# Sch_v4.net
KiCad netlist of a schematic drawn in EAGLE
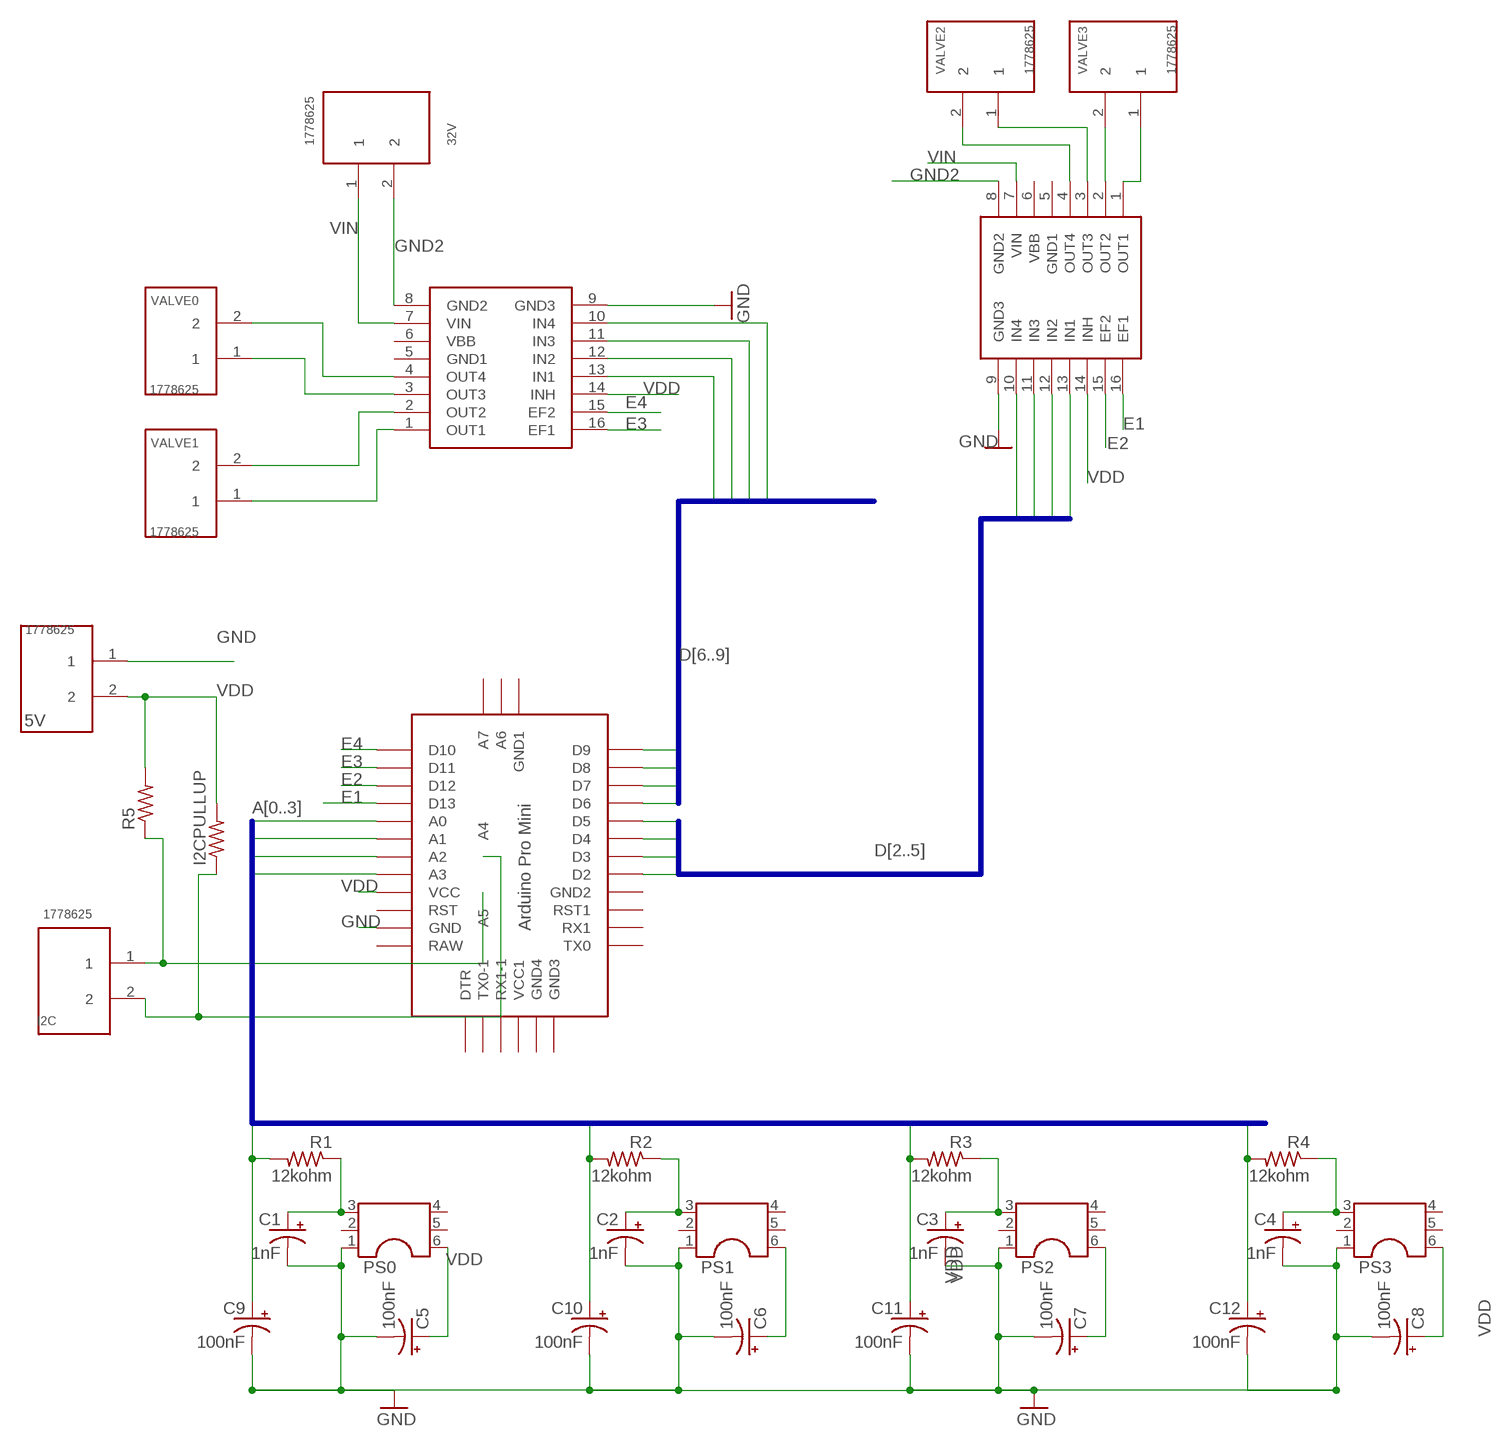
[diagram p0: schematic, sheet 1]

(export (version "E")
  (design (tool "Eeschema 10.0.6"))
  (components
    (comp (ref "5V")
      (value "1778625")
      (footprint "eagle-import:1778625")
      (fields (field (name "MF") "Phoenix Contact"))
      (libsource (lib "eagle-import") (part "1778625"))
    )
    (comp (ref "32V")
      (value "1778625")
      (footprint "eagle-import:1778625")
      (fields (field (name "MF") "Phoenix Contact"))
      (libsource (lib "eagle-import") (part "1778625"))
    )
    (comp (ref "C1")
      (value "1nF")
      (footprint "eagle-import:E2,5-5")
      (libsource (lib "eagle-import") (part "CPOL-USE2.5-5"))
    )
    (comp (ref "C2")
      (value "1nF")
      (footprint "eagle-import:E2,5-5")
      (libsource (lib "eagle-import") (part "CPOL-USE2.5-5"))
    )
    (comp (ref "C3")
      (value "1nF")
      (footprint "eagle-import:E2,5-5")
      (libsource (lib "eagle-import") (part "CPOL-USE2.5-5"))
    )
    (comp (ref "C4")
      (value "1nF")
      (footprint "eagle-import:E2,5-5")
      (libsource (lib "eagle-import") (part "CPOL-USE2.5-5"))
    )
    (comp (ref "C5")
      (value "100nF")
      (footprint "eagle-import:E2,5-5")
      (libsource (lib "eagle-import") (part "CPOL-USE2.5-5"))
    )
    (comp (ref "C6")
      (value "100nF")
      (footprint "eagle-import:E2,5-5")
      (libsource (lib "eagle-import") (part "CPOL-USE2.5-5"))
    )
    (comp (ref "C7")
      (value "100nF")
      (footprint "eagle-import:E2,5-5")
      (libsource (lib "eagle-import") (part "CPOL-USE2.5-5"))
    )
    (comp (ref "C8")
      (value "100nF")
      (footprint "eagle-import:E2,5-5")
      (libsource (lib "eagle-import") (part "CPOL-USE2.5-5"))
    )
    (comp (ref "C9")
      (value "100nF")
      (footprint "eagle-import:E2,5-5")
      (libsource (lib "eagle-import") (part "CPOL-USE2.5-5"))
    )
    (comp (ref "C10")
      (value "100nF")
      (footprint "eagle-import:E2,5-5")
      (libsource (lib "eagle-import") (part "CPOL-USE2.5-5"))
    )
    (comp (ref "C11")
      (value "100nF")
      (footprint "eagle-import:E2,5-5")
      (libsource (lib "eagle-import") (part "CPOL-USE2.5-5"))
    )
    (comp (ref "C12")
      (value "100nF")
      (footprint "eagle-import:E2,5-5")
      (libsource (lib "eagle-import") (part "CPOL-USE2.5-5"))
    )
    (comp (ref "I2C")
      (value "1778625")
      (footprint "eagle-import:1778625")
      (fields (field (name "MF") "Phoenix Contact"))
      (libsource (lib "eagle-import") (part "1778625"))
    )
    (comp (ref "I2CPULLUP")
      (value "R-US_0204/7")
      (footprint "eagle-import:0204_7")
      (libsource (lib "eagle-import") (part "R-US_0204/7"))
    )
    (comp (ref "PS0")
      (value "ABPDRNN100PGAA5")
      (footprint "eagle-import:ABPDRNN100PGAA5")
      (libsource (lib "eagle-import") (part "ABPDRNN100PGAA5"))
    )
    (comp (ref "PS1")
      (value "ABPDRNN100PGAA5")
      (footprint "eagle-import:ABPDRNN100PGAA5")
      (libsource (lib "eagle-import") (part "ABPDRNN100PGAA5"))
    )
    (comp (ref "PS2")
      (value "ABPDRNN100PGAA5")
      (footprint "eagle-import:ABPDRNN100PGAA5")
      (libsource (lib "eagle-import") (part "ABPDRNN100PGAA5"))
    )
    (comp (ref "PS3")
      (value "ABPDRNN100PGAA5")
      (footprint "eagle-import:ABPDRNN100PGAA5")
      (libsource (lib "eagle-import") (part "ABPDRNN100PGAA5"))
    )
    (comp (ref "R1")
      (value "12kohm")
      (footprint "eagle-import:0204_7")
      (libsource (lib "eagle-import") (part "R-US_0204/7"))
    )
    (comp (ref "R2")
      (value "12kohm")
      (footprint "eagle-import:0204_7")
      (libsource (lib "eagle-import") (part "R-US_0204/7"))
    )
    (comp (ref "R3")
      (value "12kohm")
      (footprint "eagle-import:0204_7")
      (libsource (lib "eagle-import") (part "R-US_0204/7"))
    )
    (comp (ref "R4")
      (value "12kohm")
      (footprint "eagle-import:0204_7")
      (libsource (lib "eagle-import") (part "R-US_0204/7"))
    )
    (comp (ref "R5")
      (value "R-US_0204/7")
      (footprint "eagle-import:0204_7")
      (libsource (lib "eagle-import") (part "R-US_0204/7"))
    )
    (comp (ref "U$1")
      (value "ABK-PRO-MINI")
      (footprint "eagle-import:ABK-PRO-MINI")
      (libsource (lib "eagle-import") (part "ABK-PRO-MINI"))
    )
    (comp (ref "U$2")
      (value "A4990")
      (footprint "eagle-import:A4990")
      (libsource (lib "eagle-import") (part "A4990"))
    )
    (comp (ref "U$3")
      (value "A4990")
      (footprint "eagle-import:A4990")
      (libsource (lib "eagle-import") (part "A4990"))
    )
    (comp (ref "VALVE0")
      (value "1778625")
      (footprint "eagle-import:1778625")
      (fields (field (name "MF") "Phoenix Contact"))
      (libsource (lib "eagle-import") (part "1778625"))
    )
    (comp (ref "VALVE1")
      (value "1778625")
      (footprint "eagle-import:1778625")
      (fields (field (name "MF") "Phoenix Contact"))
      (libsource (lib "eagle-import") (part "1778625"))
    )
    (comp (ref "VALVE2")
      (value "1778625")
      (footprint "eagle-import:1778625")
      (fields (field (name "MF") "Phoenix Contact"))
      (libsource (lib "eagle-import") (part "1778625"))
    )
    (comp (ref "VALVE3")
      (value "1778625")
      (footprint "eagle-import:1778625")
      (fields (field (name "MF") "Phoenix Contact"))
      (libsource (lib "eagle-import") (part "1778625"))
    )
  )
  (nets
    (net (code "1") (name "/A0") (class "Default")
      (node (ref "C9") (pin "+") (pinfunction "+_+") (pintype "passive"))
      (node (ref "R1") (pin "2") (pinfunction "2_2") (pintype "passive"))
      (node (ref "U$1") (pin "A0") (pinfunction "A0_A0") (pintype "bidirectional"))
    )
    (net (code "2") (name "/A1") (class "Default")
      (node (ref "C10") (pin "+") (pinfunction "+_+") (pintype "passive"))
      (node (ref "R2") (pin "2") (pinfunction "2_2") (pintype "passive"))
      (node (ref "U$1") (pin "A1") (pinfunction "A1_A1") (pintype "bidirectional"))
    )
    (net (code "3") (name "/A2") (class "Default")
      (node (ref "C11") (pin "+") (pinfunction "+_+") (pintype "passive"))
      (node (ref "R3") (pin "2") (pinfunction "2_2") (pintype "passive"))
      (node (ref "U$1") (pin "A2") (pinfunction "A2_A2") (pintype "bidirectional"))
    )
    (net (code "4") (name "/A3") (class "Default")
      (node (ref "C12") (pin "+") (pinfunction "+_+") (pintype "passive"))
      (node (ref "R4") (pin "2") (pinfunction "2_2") (pintype "passive"))
      (node (ref "U$1") (pin "A3") (pinfunction "A3_A3") (pintype "bidirectional"))
    )
    (net (code "6") (name "/D2") (class "Default")
      (node (ref "U$1") (pin "D2") (pinfunction "D2_D2") (pintype "bidirectional"))
      (node (ref "U$3") (pin "13") (pinfunction "IN1_13") (pintype "bidirectional"))
    )
    (net (code "7") (name "/D3") (class "Default")
      (node (ref "U$1") (pin "D3") (pinfunction "D3_D3") (pintype "bidirectional"))
      (node (ref "U$3") (pin "12") (pinfunction "IN2_12") (pintype "bidirectional"))
    )
    (net (code "8") (name "/D4") (class "Default")
      (node (ref "U$1") (pin "D4") (pinfunction "D4_D4") (pintype "bidirectional"))
      (node (ref "U$3") (pin "11") (pinfunction "IN3_11") (pintype "bidirectional"))
    )
    (net (code "9") (name "/D5") (class "Default")
      (node (ref "U$1") (pin "D5") (pinfunction "D5_D5") (pintype "bidirectional"))
      (node (ref "U$3") (pin "10") (pinfunction "IN4_10") (pintype "bidirectional"))
    )
    (net (code "10") (name "/D6") (class "Default")
      (node (ref "U$1") (pin "D6") (pinfunction "D6_D6") (pintype "bidirectional"))
      (node (ref "U$2") (pin "13") (pinfunction "IN1_13") (pintype "bidirectional"))
    )
    (net (code "11") (name "/D7") (class "Default")
      (node (ref "U$1") (pin "D7") (pinfunction "D7_D7") (pintype "bidirectional"))
      (node (ref "U$2") (pin "12") (pinfunction "IN2_12") (pintype "bidirectional"))
    )
    (net (code "12") (name "/D8") (class "Default")
      (node (ref "U$1") (pin "D8") (pinfunction "D8_D8") (pintype "bidirectional"))
      (node (ref "U$2") (pin "11") (pinfunction "IN3_11") (pintype "bidirectional"))
    )
    (net (code "13") (name "/D9") (class "Default")
      (node (ref "U$1") (pin "D9") (pinfunction "D9_D9") (pintype "bidirectional"))
      (node (ref "U$2") (pin "10") (pinfunction "IN4_10") (pintype "bidirectional"))
    )
    (net (code "16") (name "/E1") (class "Default")
      (node (ref "U$1") (pin "D13") (pinfunction "D13_D13") (pintype "bidirectional"))
      (node (ref "U$3") (pin "16") (pinfunction "EF1_16") (pintype "bidirectional"))
    )
    (net (code "17") (name "/E2") (class "Default")
      (node (ref "U$1") (pin "D12") (pinfunction "D12_D12") (pintype "bidirectional"))
      (node (ref "U$3") (pin "15") (pinfunction "EF2_15") (pintype "bidirectional"))
    )
    (net (code "18") (name "/E3") (class "Default")
      (node (ref "U$1") (pin "D11") (pinfunction "D11_D11") (pintype "bidirectional"))
      (node (ref "U$2") (pin "16") (pinfunction "EF1_16") (pintype "bidirectional"))
    )
    (net (code "19") (name "/E4") (class "Default")
      (node (ref "U$1") (pin "D10") (pinfunction "D10_D10") (pintype "bidirectional"))
      (node (ref "U$2") (pin "15") (pinfunction "EF2_15") (pintype "bidirectional"))
    )
    (net (code "20") (name "/GND2") (class "Default")
      (node (ref "32V") (pin "2") (pinfunction "2_2") (pintype "bidirectional"))
      (node (ref "U$2") (pin "8") (pinfunction "GND2_8") (pintype "bidirectional"))
      (node (ref "U$3") (pin "8") (pinfunction "GND2_8") (pintype "bidirectional"))
    )
    (net (code "21") (name "/VDD") (class "Default")
      (node (ref "5V") (pin "2") (pinfunction "2_2") (pintype "bidirectional"))
      (node (ref "C5") (pin "+") (pinfunction "+_+") (pintype "passive"))
      (node (ref "C6") (pin "+") (pinfunction "+_+") (pintype "passive"))
      (node (ref "C7") (pin "+") (pinfunction "+_+") (pintype "passive"))
      (node (ref "C8") (pin "+") (pinfunction "+_+") (pintype "passive"))
      (node (ref "I2C") (pin "2") (pinfunction "2_2") (pintype "bidirectional"))
      (node (ref "I2CPULLUP") (pin "1") (pinfunction "1_1") (pintype "passive"))
      (node (ref "I2CPULLUP") (pin "2") (pinfunction "2_2") (pintype "passive"))
      (node (ref "PS0") (pin "6") (pinfunction "6_6") (pintype "passive"))
      (node (ref "PS1") (pin "6") (pinfunction "6_6") (pintype "passive"))
      (node (ref "PS2") (pin "6") (pinfunction "6_6") (pintype "passive"))
      (node (ref "PS3") (pin "6") (pinfunction "6_6") (pintype "passive"))
      (node (ref "R5") (pin "2") (pinfunction "2_2") (pintype "passive"))
      (node (ref "U$1") (pin "A4") (pinfunction "A4_A4") (pintype "bidirectional"))
      (node (ref "U$1") (pin "VCC") (pinfunction "VCC_VCC") (pintype "bidirectional"))
      (node (ref "U$2") (pin "14") (pinfunction "INH_14") (pintype "bidirectional"))
      (node (ref "U$3") (pin "14") (pinfunction "INH_14") (pintype "bidirectional"))
    )
    (net (code "22") (name "/VIN") (class "Default")
      (node (ref "32V") (pin "1") (pinfunction "1_1") (pintype "bidirectional"))
      (node (ref "U$2") (pin "7") (pinfunction "VIN_7") (pintype "bidirectional"))
      (node (ref "U$3") (pin "7") (pinfunction "VIN_7") (pintype "bidirectional"))
    )
    (net (code "23") (name "GND") (class "Default")
      (node (ref "5V") (pin "1") (pinfunction "1_1") (pintype "bidirectional"))
      (node (ref "C1") (pin "-") (pinfunction "-_-") (pintype "passive"))
      (node (ref "C10") (pin "-") (pinfunction "-_-") (pintype "passive"))
      (node (ref "C11") (pin "-") (pinfunction "-_-") (pintype "passive"))
      (node (ref "C12") (pin "-") (pinfunction "-_-") (pintype "passive"))
      (node (ref "C2") (pin "-") (pinfunction "-_-") (pintype "passive"))
      (node (ref "C3") (pin "-") (pinfunction "-_-") (pintype "passive"))
      (node (ref "C4") (pin "-") (pinfunction "-_-") (pintype "passive"))
      (node (ref "C5") (pin "-") (pinfunction "-_-") (pintype "passive"))
      (node (ref "C6") (pin "-") (pinfunction "-_-") (pintype "passive"))
      (node (ref "C7") (pin "-") (pinfunction "-_-") (pintype "passive"))
      (node (ref "C8") (pin "-") (pinfunction "-_-") (pintype "passive"))
      (node (ref "C9") (pin "-") (pinfunction "-_-") (pintype "passive"))
      (node (ref "PS0") (pin "1") (pinfunction "1_1") (pintype "passive"))
      (node (ref "PS1") (pin "1") (pinfunction "1_1") (pintype "passive"))
      (node (ref "PS2") (pin "1") (pinfunction "1_1") (pintype "passive"))
      (node (ref "PS3") (pin "1") (pinfunction "1_1") (pintype "passive"))
      (node (ref "U$1") (pin "GND") (pinfunction "GND_GND") (pintype "bidirectional"))
      (node (ref "U$2") (pin "9") (pinfunction "GND3_9") (pintype "bidirectional"))
      (node (ref "U$3") (pin "9") (pinfunction "GND3_9") (pintype "bidirectional"))
    )
    (net (code "24") (name "Net-(C1-Pad+)") (class "Default")
      (node (ref "C1") (pin "+") (pinfunction "+_+") (pintype "passive"))
      (node (ref "PS0") (pin "3") (pinfunction "3_3") (pintype "passive"))
      (node (ref "R1") (pin "1") (pinfunction "1_1") (pintype "passive"))
    )
    (net (code "25") (name "Net-(C2-Pad+)") (class "Default")
      (node (ref "C2") (pin "+") (pinfunction "+_+") (pintype "passive"))
      (node (ref "PS1") (pin "3") (pinfunction "3_3") (pintype "passive"))
      (node (ref "R2") (pin "1") (pinfunction "1_1") (pintype "passive"))
    )
    (net (code "26") (name "Net-(C3-Pad+)") (class "Default")
      (node (ref "C3") (pin "+") (pinfunction "+_+") (pintype "passive"))
      (node (ref "PS2") (pin "3") (pinfunction "3_3") (pintype "passive"))
      (node (ref "R3") (pin "1") (pinfunction "1_1") (pintype "passive"))
    )
    (net (code "27") (name "Net-(C4-Pad+)") (class "Default")
      (node (ref "C4") (pin "+") (pinfunction "+_+") (pintype "passive"))
      (node (ref "PS3") (pin "3") (pinfunction "3_3") (pintype "passive"))
      (node (ref "R4") (pin "1") (pinfunction "1_1") (pintype "passive"))
    )
    (net (code "28") (name "Net-(I2C-Pad1)") (class "Default")
      (node (ref "I2C") (pin "1") (pinfunction "1_1") (pintype "bidirectional"))
      (node (ref "R5") (pin "1") (pinfunction "1_1") (pintype "passive"))
      (node (ref "U$1") (pin "A5") (pinfunction "A5_A5") (pintype "bidirectional"))
    )
    (net (code "29") (name "Net-(U$2-OUT1)") (class "Default")
      (node (ref "U$2") (pin "1") (pinfunction "OUT1_1") (pintype "bidirectional"))
      (node (ref "VALVE1") (pin "1") (pinfunction "1_1") (pintype "bidirectional"))
    )
    (net (code "30") (name "Net-(U$2-OUT2)") (class "Default")
      (node (ref "U$2") (pin "2") (pinfunction "OUT2_2") (pintype "bidirectional"))
      (node (ref "VALVE1") (pin "2") (pinfunction "2_2") (pintype "bidirectional"))
    )
    (net (code "31") (name "Net-(U$2-OUT3)") (class "Default")
      (node (ref "U$2") (pin "3") (pinfunction "OUT3_3") (pintype "bidirectional"))
      (node (ref "VALVE0") (pin "1") (pinfunction "1_1") (pintype "bidirectional"))
    )
    (net (code "32") (name "Net-(U$2-OUT4)") (class "Default")
      (node (ref "U$2") (pin "4") (pinfunction "OUT4_4") (pintype "bidirectional"))
      (node (ref "VALVE0") (pin "2") (pinfunction "2_2") (pintype "bidirectional"))
    )
    (net (code "33") (name "Net-(U$3-OUT1)") (class "Default")
      (node (ref "U$3") (pin "1") (pinfunction "OUT1_1") (pintype "bidirectional"))
      (node (ref "VALVE3") (pin "1") (pinfunction "1_1") (pintype "bidirectional"))
    )
    (net (code "34") (name "Net-(U$3-OUT2)") (class "Default")
      (node (ref "U$3") (pin "2") (pinfunction "OUT2_2") (pintype "bidirectional"))
      (node (ref "VALVE3") (pin "2") (pinfunction "2_2") (pintype "bidirectional"))
    )
    (net (code "35") (name "Net-(U$3-OUT3)") (class "Default")
      (node (ref "U$3") (pin "3") (pinfunction "OUT3_3") (pintype "bidirectional"))
      (node (ref "VALVE2") (pin "1") (pinfunction "1_1") (pintype "bidirectional"))
    )
    (net (code "36") (name "Net-(U$3-OUT4)") (class "Default")
      (node (ref "U$3") (pin "4") (pinfunction "OUT4_4") (pintype "bidirectional"))
      (node (ref "VALVE2") (pin "2") (pinfunction "2_2") (pintype "bidirectional"))
    )
    (net (code "37") (name "unconnected-(PS0-Pad2)") (class "Default")
      (node (ref "PS0") (pin "2") (pinfunction "2_2") (pintype "passive"))
    )
    (net (code "38") (name "unconnected-(PS0-Pad4)") (class "Default")
      (node (ref "PS0") (pin "4") (pinfunction "4_4") (pintype "passive"))
    )
    (net (code "39") (name "unconnected-(PS0-Pad5)") (class "Default")
      (node (ref "PS0") (pin "5") (pinfunction "5_5") (pintype "passive"))
    )
    (net (code "40") (name "unconnected-(PS1-Pad2)") (class "Default")
      (node (ref "PS1") (pin "2") (pinfunction "2_2") (pintype "passive"))
    )
    (net (code "41") (name "unconnected-(PS1-Pad4)") (class "Default")
      (node (ref "PS1") (pin "4") (pinfunction "4_4") (pintype "passive"))
    )
    (net (code "42") (name "unconnected-(PS1-Pad5)") (class "Default")
      (node (ref "PS1") (pin "5") (pinfunction "5_5") (pintype "passive"))
    )
    (net (code "43") (name "unconnected-(PS2-Pad2)") (class "Default")
      (node (ref "PS2") (pin "2") (pinfunction "2_2") (pintype "passive"))
    )
    (net (code "44") (name "unconnected-(PS2-Pad4)") (class "Default")
      (node (ref "PS2") (pin "4") (pinfunction "4_4") (pintype "passive"))
    )
    (net (code "45") (name "unconnected-(PS2-Pad5)") (class "Default")
      (node (ref "PS2") (pin "5") (pinfunction "5_5") (pintype "passive"))
    )
    (net (code "46") (name "unconnected-(PS3-Pad2)") (class "Default")
      (node (ref "PS3") (pin "2") (pinfunction "2_2") (pintype "passive"))
    )
    (net (code "47") (name "unconnected-(PS3-Pad4)") (class "Default")
      (node (ref "PS3") (pin "4") (pinfunction "4_4") (pintype "passive"))
    )
    (net (code "48") (name "unconnected-(PS3-Pad5)") (class "Default")
      (node (ref "PS3") (pin "5") (pinfunction "5_5") (pintype "passive"))
    )
    (net (code "49") (name "unconnected-(U$1-GND1-PadGND4)") (class "Default")
      (node (ref "U$1") (pin "GND4") (pinfunction "GND1_GND4") (pintype "bidirectional"))
    )
    (net (code "50") (name "unconnected-(U$1-GND2-PadGND1)") (class "Default")
      (node (ref "U$1") (pin "GND1") (pinfunction "GND2_GND1") (pintype "bidirectional"))
    )
    (net (code "51") (name "unconnected-(U$1-GND3-PadGND2)") (class "Default")
      (node (ref "U$1") (pin "GND2") (pinfunction "GND3_GND2") (pintype "bidirectional"))
    )
    (net (code "52") (name "unconnected-(U$1-GND4-PadGND3)") (class "Default")
      (node (ref "U$1") (pin "GND3") (pinfunction "GND4_GND3") (pintype "bidirectional"))
    )
    (net (code "53") (name "unconnected-(U$1-PadA6)") (class "Default")
      (node (ref "U$1") (pin "A6") (pinfunction "A6_A6") (pintype "bidirectional"))
    )
    (net (code "54") (name "unconnected-(U$1-PadA7)") (class "Default")
      (node (ref "U$1") (pin "A7") (pinfunction "A7_A7") (pintype "bidirectional"))
    )
    (net (code "55") (name "unconnected-(U$1-PadDTR)") (class "Default")
      (node (ref "U$1") (pin "DTR") (pinfunction "DTR_DTR") (pintype "bidirectional"))
    )
    (net (code "56") (name "unconnected-(U$1-PadRAW)") (class "Default")
      (node (ref "U$1") (pin "RAW") (pinfunction "RAW_RAW") (pintype "bidirectional"))
    )
    (net (code "57") (name "unconnected-(U$1-PadRST)") (class "Default")
      (node (ref "U$1") (pin "RST") (pinfunction "RST_RST") (pintype "bidirectional"))
    )
    (net (code "58") (name "unconnected-(U$1-PadRST1)") (class "Default")
      (node (ref "U$1") (pin "RST1") (pinfunction "RST1_RST1") (pintype "bidirectional"))
    )
    (net (code "59") (name "unconnected-(U$1-PadRX1)") (class "Default")
      (node (ref "U$1") (pin "RX1") (pinfunction "RX1_RX1") (pintype "bidirectional"))
    )
    (net (code "60") (name "unconnected-(U$1-PadRX1-1)") (class "Default")
      (node (ref "U$1") (pin "RX1-1") (pinfunction "RX1-1_RX1-1") (pintype "bidirectional"))
    )
    (net (code "61") (name "unconnected-(U$1-PadTX0)") (class "Default")
      (node (ref "U$1") (pin "TX0") (pinfunction "TX0_TX0") (pintype "bidirectional"))
    )
    (net (code "62") (name "unconnected-(U$1-PadTX0-1)") (class "Default")
      (node (ref "U$1") (pin "TX0-1") (pinfunction "TX0-1_TX0-1") (pintype "bidirectional"))
    )
    (net (code "63") (name "unconnected-(U$1-PadVCC1)") (class "Default")
      (node (ref "U$1") (pin "VCC1") (pinfunction "VCC1_VCC1") (pintype "bidirectional"))
    )
    (net (code "64") (name "unconnected-(U$2-GND1-Pad5)") (class "Default")
      (node (ref "U$2") (pin "5") (pinfunction "GND1_5") (pintype "bidirectional"))
    )
    (net (code "65") (name "unconnected-(U$2-VBB-Pad6)") (class "Default")
      (node (ref "U$2") (pin "6") (pinfunction "VBB_6") (pintype "bidirectional"))
    )
    (net (code "66") (name "unconnected-(U$3-GND1-Pad5)") (class "Default")
      (node (ref "U$3") (pin "5") (pinfunction "GND1_5") (pintype "bidirectional"))
    )
    (net (code "67") (name "unconnected-(U$3-VBB-Pad6)") (class "Default")
      (node (ref "U$3") (pin "6") (pinfunction "VBB_6") (pintype "bidirectional"))
    )
  )
)
